# SOLAR_13_8V_VERSION_2.net
KiCad netlist of a schematic drawn in EAGLE
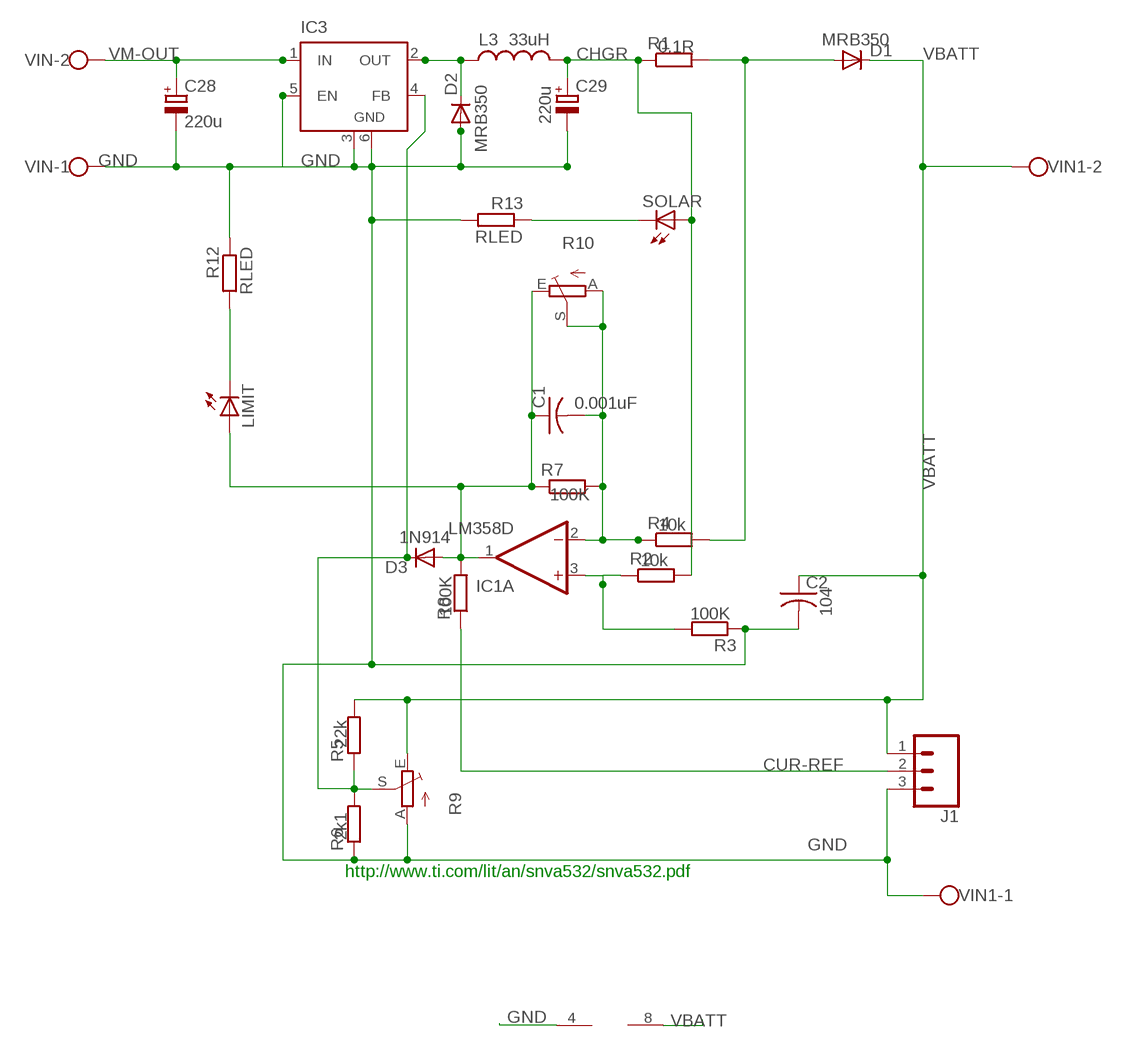
[diagram p0: schematic, sheet 1]

(export (version "E")
  (design (tool "Eeschema 10.0.6"))
  (components
    (comp (ref "C1")
      (value "0.001uF")
      (footprint "eagle-import:C1206")
      (libsource (lib "eagle-import") (part "C-USC1206"))
    )
    (comp (ref "C2")
      (value "104")
      (footprint "eagle-import:C1206")
      (libsource (lib "eagle-import") (part "C-USC1206"))
    )
    (comp (ref "C28")
      (value "220u")
      (footprint "eagle-import:E3,5-10")
      (libsource (lib "eagle-import") (part "CPOL-EUE3.5-10"))
    )
    (comp (ref "C29")
      (value "220u")
      (footprint "eagle-import:E3,5-10")
      (libsource (lib "eagle-import") (part "CPOL-EUE3.5-10"))
    )
    (comp (ref "D1")
      (value "MRB350")
      (footprint "eagle-import:DO-214AC")
      (libsource (lib "eagle-import") (part "DIODE-DO-214AC"))
    )
    (comp (ref "D2")
      (value "MRB350")
      (footprint "eagle-import:DO-214AC")
      (libsource (lib "eagle-import") (part "DIODE-DO-214AC"))
    )
    (comp (ref "D3")
      (value "1N914")
      (footprint "eagle-import:DO-214AC")
      (libsource (lib "eagle-import") (part "DIODE-DO-214AC"))
    )
    (comp (ref "IC1")
      (value "LM358D")
      (footprint "eagle-import:SO08")
      (libsource (lib "eagle-import") (part "LMV358?MX"))
    )
    (comp (ref "IC3")
      (value "LM2596S")
      (footprint "eagle-import:TO263-5")
      (libsource (lib "eagle-import") (part "LM2596S"))
    )
    (comp (ref "J1")
      (value "CONN_03")
      (footprint "eagle-import:1X03")
      (libsource (lib "eagle-import") (part "CONN_03"))
    )
    (comp (ref "L3")
      (value "33uH")
      (footprint "eagle-import:CDRH125")
      (libsource (lib "eagle-import") (part "INDUCTORPWR"))
    )
    (comp (ref "LIMIT")
      (value "LED3MM")
      (footprint "eagle-import:LED3MM")
      (libsource (lib "eagle-import") (part "LED3MM"))
    )
    (comp (ref "R1")
      (value "0.1R")
      (footprint "eagle-import:R2512")
      (libsource (lib "eagle-import") (part "R-EU_R2512"))
    )
    (comp (ref "R2")
      (value "10k")
      (footprint "eagle-import:R1206")
      (libsource (lib "eagle-import") (part "R-EU_R1206"))
    )
    (comp (ref "R3")
      (value "100K")
      (footprint "eagle-import:R1206")
      (libsource (lib "eagle-import") (part "R-EU_R1206"))
    )
    (comp (ref "R4")
      (value "10k")
      (footprint "eagle-import:R1206")
      (libsource (lib "eagle-import") (part "R-EU_R1206"))
    )
    (comp (ref "R5")
      (value "22k")
      (footprint "eagle-import:R1206")
      (libsource (lib "eagle-import") (part "R-EU_R1206"))
    )
    (comp (ref "R6")
      (value "2k1")
      (footprint "eagle-import:R1206")
      (libsource (lib "eagle-import") (part "R-EU_R1206"))
    )
    (comp (ref "R7")
      (value "100K")
      (footprint "eagle-import:R1206")
      (libsource (lib "eagle-import") (part "R-EU_R1206"))
    )
    (comp (ref "R8")
      (value "100K")
      (footprint "eagle-import:R1206")
      (libsource (lib "eagle-import") (part "R-EU_R1206"))
    )
    (comp (ref "R9")
      (value "TRIM_EU-B25P")
      (footprint "eagle-import:B25P")
      (libsource (lib "eagle-import") (part "TRIM_EU-B25P"))
    )
    (comp (ref "R10")
      (value "TRIM_EU-B25P")
      (footprint "eagle-import:B25P")
      (libsource (lib "eagle-import") (part "TRIM_EU-B25P"))
    )
    (comp (ref "R12")
      (value "RLED")
      (footprint "eagle-import:R1206")
      (libsource (lib "eagle-import") (part "R-EU_R1206"))
    )
    (comp (ref "R13")
      (value "RLED")
      (footprint "eagle-import:R1206")
      (libsource (lib "eagle-import") (part "R-EU_R1206"))
    )
    (comp (ref "SOLAR")
      (value "LED3MM")
      (footprint "eagle-import:LED3MM")
      (libsource (lib "eagle-import") (part "LED3MM"))
    )
    (comp (ref "VIN")
      (value "W237-102")
      (footprint "eagle-import:W237-102")
      (fields (field (name "MPN") "237-102"))
      (libsource (lib "eagle-import") (part "W237-102"))
    )
    (comp (ref "VIN1")
      (value "W237-102")
      (footprint "eagle-import:W237-102")
      (fields (field (name "MPN") "237-102"))
      (libsource (lib "eagle-import") (part "W237-102"))
    )
  )
  (nets
    (net (code "1") (name "/CHGR") (class "Default")
      (node (ref "C29") (pin "+") (pinfunction "+_+") (pintype "passive"))
      (node (ref "L3") (pin "2") (pinfunction "2_2") (pintype "passive"))
      (node (ref "R1") (pin "1") (pinfunction "1_1") (pintype "passive"))
      (node (ref "R2") (pin "2") (pinfunction "2_2") (pintype "passive"))
      (node (ref "SOLAR") (pin "A") (pinfunction "A_A") (pintype "passive"))
    )
    (net (code "2") (name "/CUR-REF") (class "Default")
      (node (ref "J1") (pin "2") (pinfunction "2_2") (pintype "passive"))
      (node (ref "R8") (pin "1") (pinfunction "1_1") (pintype "passive"))
    )
    (net (code "3") (name "/GND") (class "Default")
      (node (ref "C2") (pin "2") (pinfunction "2_2") (pintype "passive"))
      (node (ref "C28") (pin "-") (pinfunction "-_-") (pintype "passive"))
      (node (ref "C29") (pin "-") (pinfunction "-_-") (pintype "passive"))
      (node (ref "D2") (pin "2") (pinfunction "A_2") (pintype "passive"))
      (node (ref "IC1") (pin "4") (pinfunction "V-_4") (pintype "power_in"))
      (node (ref "IC3") (pin "3") (pinfunction "GND_3") (pintype "power_in"))
      (node (ref "IC3") (pin "5") (pinfunction "EN_5") (pintype "input"))
      (node (ref "IC3") (pin "6") (pinfunction "GND_6") (pintype "power_in"))
      (node (ref "J1") (pin "3") (pinfunction "3_3") (pintype "passive"))
      (node (ref "R12") (pin "1") (pinfunction "1_1") (pintype "passive"))
      (node (ref "R13") (pin "2") (pinfunction "2_2") (pintype "passive"))
      (node (ref "R3") (pin "1") (pinfunction "1_1") (pintype "passive"))
      (node (ref "R6") (pin "1") (pinfunction "1_1") (pintype "passive"))
      (node (ref "R9") (pin "A") (pinfunction "A_A") (pintype "passive"))
      (node (ref "VIN") (pin "1") (pinfunction "KL_1") (pintype "passive"))
      (node (ref "VIN1") (pin "1") (pinfunction "KL_1") (pintype "passive"))
    )
    (net (code "4") (name "/VBATT") (class "Default")
      (node (ref "C2") (pin "1") (pinfunction "1_1") (pintype "passive"))
      (node (ref "D1") (pin "1") (pinfunction "C_1") (pintype "passive"))
      (node (ref "IC1") (pin "8") (pinfunction "V+_8") (pintype "power_in"))
      (node (ref "J1") (pin "1") (pinfunction "1_1") (pintype "passive"))
      (node (ref "R5") (pin "2") (pinfunction "2_2") (pintype "passive"))
      (node (ref "R9") (pin "E") (pinfunction "E_E") (pintype "passive"))
      (node (ref "VIN1") (pin "2") (pinfunction "KL_2") (pintype "passive"))
    )
    (net (code "5") (name "/VM-OUT") (class "Default")
      (node (ref "C28") (pin "+") (pinfunction "+_+") (pintype "passive"))
      (node (ref "IC3") (pin "1") (pinfunction "IN_1") (pintype "input"))
      (node (ref "VIN") (pin "2") (pinfunction "KL_2") (pintype "passive"))
    )
    (net (code "6") (name "Net-(D1-A)") (class "Default")
      (node (ref "D1") (pin "2") (pinfunction "A_2") (pintype "passive"))
      (node (ref "R1") (pin "2") (pinfunction "2_2") (pintype "passive"))
      (node (ref "R4") (pin "2") (pinfunction "2_2") (pintype "passive"))
    )
    (net (code "7") (name "Net-(D2-C)") (class "Default")
      (node (ref "D2") (pin "1") (pinfunction "C_1") (pintype "passive"))
      (node (ref "IC3") (pin "2") (pinfunction "OUT_2") (pintype "output"))
      (node (ref "L3") (pin "1") (pinfunction "1_1") (pintype "passive"))
    )
    (net (code "8") (name "Net-(D3-A)") (class "Default")
      (node (ref "C1") (pin "1") (pinfunction "1_1") (pintype "passive"))
      (node (ref "D3") (pin "2") (pinfunction "A_2") (pintype "passive"))
      (node (ref "IC1") (pin "1") (pinfunction "OUT_1") (pintype "output"))
      (node (ref "LIMIT") (pin "A") (pinfunction "A_A") (pintype "passive"))
      (node (ref "R10") (pin "E") (pinfunction "E_E") (pintype "passive"))
      (node (ref "R7") (pin "1") (pinfunction "1_1") (pintype "passive"))
      (node (ref "R8") (pin "2") (pinfunction "2_2") (pintype "passive"))
    )
    (net (code "9") (name "Net-(D3-C)") (class "Default")
      (node (ref "D3") (pin "1") (pinfunction "C_1") (pintype "passive"))
      (node (ref "IC3") (pin "4") (pinfunction "FB_4") (pintype "input"))
      (node (ref "R5") (pin "1") (pinfunction "1_1") (pintype "passive"))
      (node (ref "R6") (pin "2") (pinfunction "2_2") (pintype "passive"))
      (node (ref "R9") (pin "S") (pinfunction "S_S") (pintype "passive"))
    )
    (net (code "10") (name "Net-(IC1A-+IN)") (class "Default")
      (node (ref "IC1") (pin "3") (pinfunction "+IN_3") (pintype "input"))
      (node (ref "R2") (pin "1") (pinfunction "1_1") (pintype "passive"))
      (node (ref "R3") (pin "2") (pinfunction "2_2") (pintype "passive"))
    )
    (net (code "11") (name "Net-(IC1A--IN)") (class "Default")
      (node (ref "C1") (pin "2") (pinfunction "2_2") (pintype "passive"))
      (node (ref "IC1") (pin "2") (pinfunction "-IN_2") (pintype "input"))
      (node (ref "R10") (pin "A") (pinfunction "A_A") (pintype "passive"))
      (node (ref "R10") (pin "S") (pinfunction "S_S") (pintype "passive"))
      (node (ref "R4") (pin "1") (pinfunction "1_1") (pintype "passive"))
      (node (ref "R7") (pin "2") (pinfunction "2_2") (pintype "passive"))
    )
    (net (code "12") (name "Net-(LIMIT-C)") (class "Default")
      (node (ref "LIMIT") (pin "K") (pinfunction "C_K") (pintype "passive"))
      (node (ref "R12") (pin "2") (pinfunction "2_2") (pintype "passive"))
    )
    (net (code "13") (name "Net-(SOLAR-C)") (class "Default")
      (node (ref "R13") (pin "1") (pinfunction "1_1") (pintype "passive"))
      (node (ref "SOLAR") (pin "K") (pinfunction "C_K") (pintype "passive"))
    )
  )
)
